# Self_Balancing_Bot1.net
KiCad netlist of a schematic drawn in EAGLE
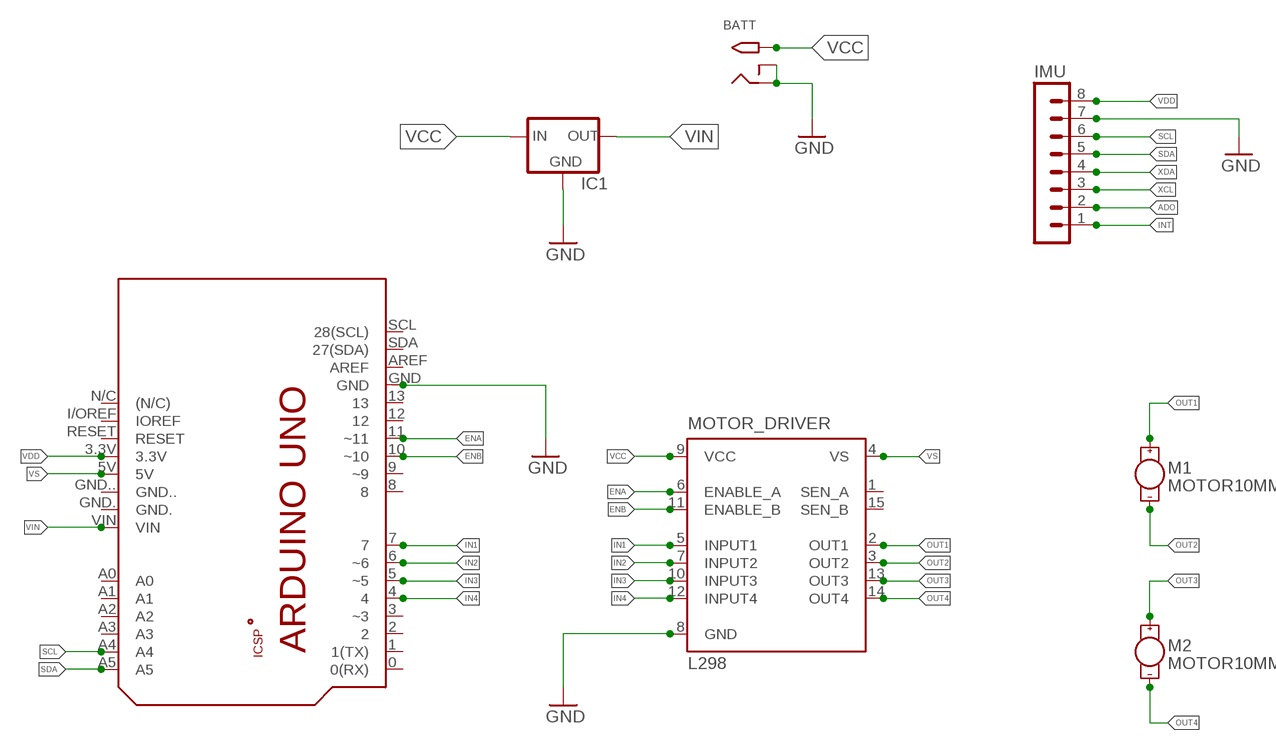
[diagram p0: schematic, sheet 1]

(export (version "E")
  (design (tool "Eeschema 10.0.6"))
  (components
    (comp (ref "ARDUINO_UNO")
      (value "ARDUINO_UNO")
      (footprint "eagle-import:ARDUINO_UNO")
      (libsource (lib "eagle-import") (part "ARDUINO_UNO"))
    )
    (comp (ref "BATT")
      (value "2.1MM_POWER_JACKTHM")
      (footprint "eagle-import:POWER_JACK")
      (libsource (lib "eagle-import") (part "2.1MM_POWER_JACKTHM"))
    )
    (comp (ref "IC1")
      (value "VOLTAGE_REGULATOR_78XXS")
      (footprint "eagle-import:78XXS")
      (libsource (lib "eagle-import") (part "VOLTAGE_REGULATOR_78XXS"))
    )
    (comp (ref "IMU")
      (value "RELIMATE_08-1")
      (footprint "eagle-import:MA08-1")
      (libsource (lib "eagle-import") (part "RELIMATE_08-1"))
    )
    (comp (ref "M1")
      (value "MOTOR10MM")
      (footprint "eagle-import:VIBE-MOTOR-10MM")
      (libsource (lib "eagle-import") (part "MOTOR10MM"))
    )
    (comp (ref "M2")
      (value "MOTOR10MM")
      (footprint "eagle-import:VIBE-MOTOR-10MM")
      (libsource (lib "eagle-import") (part "MOTOR10MM"))
    )
    (comp (ref "MOTOR_DRIVER")
      (value "L298")
      (footprint "eagle-import:MULTIWATT-15")
      (libsource (lib "eagle-import") (part "L298"))
    )
  )
  (nets
    (net (code "1") (name "ADO") (class "Default")
      (node (ref "IMU") (pin "2") (pinfunction "2_2") (pintype "passive"))
    )
    (net (code "2") (name "ENA") (class "Default")
      (node (ref "ARDUINO_UNO") (pin "11") (pinfunction "~{11}_11") (pintype "bidirectional"))
      (node (ref "MOTOR_DRIVER") (pin "6") (pinfunction "ENABLE_A_6") (pintype "input"))
    )
    (net (code "3") (name "ENB") (class "Default")
      (node (ref "ARDUINO_UNO") (pin "10") (pinfunction "~{10}_10") (pintype "bidirectional"))
      (node (ref "MOTOR_DRIVER") (pin "11") (pinfunction "ENABLE_B_11") (pintype "input"))
    )
    (net (code "4") (name "GND") (class "Default")
      (node (ref "ARDUINO_UNO") (pin "GND") (pinfunction "GND_GND") (pintype "bidirectional"))
      (node (ref "BATT") (pin "RING") (pinfunction "RING_RING") (pintype "bidirectional"))
      (node (ref "BATT") (pin "RING_SW") (pinfunction "RING_SW_RING_SW") (pintype "bidirectional"))
      (node (ref "IC1") (pin "GND") (pinfunction "GND_GND") (pintype "input"))
      (node (ref "IMU") (pin "7") (pinfunction "7_7") (pintype "passive"))
      (node (ref "MOTOR_DRIVER") (pin "8") (pinfunction "GND_8") (pintype "power_in"))
    )
    (net (code "5") (name "IN1") (class "Default")
      (node (ref "ARDUINO_UNO") (pin "7") (pinfunction "7_7") (pintype "bidirectional"))
      (node (ref "MOTOR_DRIVER") (pin "5") (pinfunction "INPUT1_5") (pintype "input"))
    )
    (net (code "6") (name "IN2") (class "Default")
      (node (ref "ARDUINO_UNO") (pin "6") (pinfunction "~{6}_6") (pintype "bidirectional"))
      (node (ref "MOTOR_DRIVER") (pin "7") (pinfunction "INPUT2_7") (pintype "input"))
    )
    (net (code "7") (name "IN3") (class "Default")
      (node (ref "ARDUINO_UNO") (pin "5") (pinfunction "~{5}_5") (pintype "bidirectional"))
      (node (ref "MOTOR_DRIVER") (pin "10") (pinfunction "INPUT3_10") (pintype "input"))
    )
    (net (code "8") (name "IN4") (class "Default")
      (node (ref "ARDUINO_UNO") (pin "4") (pinfunction "4_4") (pintype "bidirectional"))
      (node (ref "MOTOR_DRIVER") (pin "12") (pinfunction "INPUT4_12") (pintype "input"))
    )
    (net (code "9") (name "INT") (class "Default")
      (node (ref "IMU") (pin "1") (pinfunction "1_1") (pintype "passive"))
    )
    (net (code "10") (name "OUT1") (class "Default")
      (node (ref "M1") (pin "+") (pinfunction "+_+") (pintype "bidirectional"))
      (node (ref "MOTOR_DRIVER") (pin "2") (pinfunction "OUT1_2") (pintype "output"))
    )
    (net (code "11") (name "OUT2") (class "Default")
      (node (ref "M1") (pin "-") (pinfunction "-_-") (pintype "bidirectional"))
      (node (ref "MOTOR_DRIVER") (pin "3") (pinfunction "OUT2_3") (pintype "output"))
    )
    (net (code "12") (name "OUT3") (class "Default")
      (node (ref "M2") (pin "+") (pinfunction "+_+") (pintype "bidirectional"))
      (node (ref "MOTOR_DRIVER") (pin "13") (pinfunction "OUT3_13") (pintype "output"))
    )
    (net (code "13") (name "OUT4") (class "Default")
      (node (ref "M2") (pin "-") (pinfunction "-_-") (pintype "bidirectional"))
      (node (ref "MOTOR_DRIVER") (pin "14") (pinfunction "OUT4_14") (pintype "output"))
    )
    (net (code "14") (name "SCL") (class "Default")
      (node (ref "ARDUINO_UNO") (pin "A4") (pinfunction "A4_A4") (pintype "bidirectional"))
      (node (ref "IMU") (pin "6") (pinfunction "6_6") (pintype "passive"))
    )
    (net (code "15") (name "SDA") (class "Default")
      (node (ref "ARDUINO_UNO") (pin "A5") (pinfunction "A5_A5") (pintype "bidirectional"))
      (node (ref "IMU") (pin "5") (pinfunction "5_5") (pintype "passive"))
    )
    (net (code "16") (name "VCC") (class "Default")
      (node (ref "BATT") (pin "TIP") (pinfunction "TIP_TIP") (pintype "bidirectional"))
      (node (ref "IC1") (pin "IN") (pinfunction "IN_IN") (pintype "input"))
      (node (ref "MOTOR_DRIVER") (pin "9") (pinfunction "VCC_9") (pintype "power_in"))
    )
    (net (code "17") (name "VDD") (class "Default")
      (node (ref "ARDUINO_UNO") (pin "3.3V") (pinfunction "3.3V_3.3V") (pintype "bidirectional"))
      (node (ref "IMU") (pin "8") (pinfunction "8_8") (pintype "passive"))
    )
    (net (code "18") (name "VIN") (class "Default")
      (node (ref "ARDUINO_UNO") (pin "VIN") (pinfunction "VIN_VIN") (pintype "bidirectional"))
      (node (ref "IC1") (pin "OUT") (pinfunction "OUT_OUT") (pintype "passive"))
    )
    (net (code "19") (name "VS") (class "Default")
      (node (ref "ARDUINO_UNO") (pin "5V") (pinfunction "5V_5V") (pintype "bidirectional"))
      (node (ref "MOTOR_DRIVER") (pin "4") (pinfunction "VS_4") (pintype "power_in"))
    )
    (net (code "20") (name "XCL") (class "Default")
      (node (ref "IMU") (pin "3") (pinfunction "3_3") (pintype "passive"))
    )
    (net (code "21") (name "XDA") (class "Default")
      (node (ref "IMU") (pin "4") (pinfunction "4_4") (pintype "passive"))
    )
    (net (code "22") (name "unconnected-(ARDUINO_UNO-(N{slash}C)-PadN{slash}C)") (class "Default")
      (node (ref "ARDUINO_UNO") (pin "N/C") (pinfunction "(N/C)_N/C") (pintype "bidirectional"))
    )
    (net (code "23") (name "unconnected-(ARDUINO_UNO-0(RX)-Pad0)") (class "Default")
      (node (ref "ARDUINO_UNO") (pin "0") (pinfunction "0(RX)_0") (pintype "bidirectional"))
    )
    (net (code "24") (name "unconnected-(ARDUINO_UNO-1(TX)-Pad1)") (class "Default")
      (node (ref "ARDUINO_UNO") (pin "1") (pinfunction "1(TX)_1") (pintype "bidirectional"))
    )
    (net (code "25") (name "unconnected-(ARDUINO_UNO-27(SDA)-PadSDA)") (class "Default")
      (node (ref "ARDUINO_UNO") (pin "SDA") (pinfunction "27(SDA)_SDA") (pintype "bidirectional"))
    )
    (net (code "26") (name "unconnected-(ARDUINO_UNO-28(SCL)-PadSCL)") (class "Default")
      (node (ref "ARDUINO_UNO") (pin "SCL") (pinfunction "28(SCL)_SCL") (pintype "bidirectional"))
    )
    (net (code "27") (name "unconnected-(ARDUINO_UNO-IOREF-PadI{slash}OREF)") (class "Default")
      (node (ref "ARDUINO_UNO") (pin "I/OREF") (pinfunction "IOREF_I/OREF") (pintype "bidirectional"))
    )
    (net (code "28") (name "unconnected-(ARDUINO_UNO-Pad+5V)") (class "Default")
      (node (ref "ARDUINO_UNO") (pin "+5V") (pinfunction "+5V_+5V") (pintype "bidirectional"))
    )
    (net (code "29") (name "unconnected-(ARDUINO_UNO-Pad2)") (class "Default")
      (node (ref "ARDUINO_UNO") (pin "2") (pinfunction "2_2") (pintype "bidirectional"))
    )
    (net (code "30") (name "unconnected-(ARDUINO_UNO-Pad8)") (class "Default")
      (node (ref "ARDUINO_UNO") (pin "8") (pinfunction "8_8") (pintype "bidirectional"))
    )
    (net (code "31") (name "unconnected-(ARDUINO_UNO-Pad12)") (class "Default")
      (node (ref "ARDUINO_UNO") (pin "12") (pinfunction "12_12") (pintype "bidirectional"))
    )
    (net (code "32") (name "unconnected-(ARDUINO_UNO-Pad13)") (class "Default")
      (node (ref "ARDUINO_UNO") (pin "13") (pinfunction "13_13") (pintype "bidirectional"))
    )
    (net (code "33") (name "unconnected-(ARDUINO_UNO-PadA0)") (class "Default")
      (node (ref "ARDUINO_UNO") (pin "A0") (pinfunction "A0_A0") (pintype "bidirectional"))
    )
    (net (code "34") (name "unconnected-(ARDUINO_UNO-PadA1)") (class "Default")
      (node (ref "ARDUINO_UNO") (pin "A1") (pinfunction "A1_A1") (pintype "bidirectional"))
    )
    (net (code "35") (name "unconnected-(ARDUINO_UNO-PadA2)") (class "Default")
      (node (ref "ARDUINO_UNO") (pin "A2") (pinfunction "A2_A2") (pintype "bidirectional"))
    )
    (net (code "36") (name "unconnected-(ARDUINO_UNO-PadA3)") (class "Default")
      (node (ref "ARDUINO_UNO") (pin "A3") (pinfunction "A3_A3") (pintype "bidirectional"))
    )
    (net (code "37") (name "unconnected-(ARDUINO_UNO-PadAREF)") (class "Default")
      (node (ref "ARDUINO_UNO") (pin "AREF") (pinfunction "AREF_AREF") (pintype "bidirectional"))
    )
    (net (code "38") (name "unconnected-(ARDUINO_UNO-PadGND.)") (class "Default")
      (node (ref "ARDUINO_UNO") (pin "GND.") (pinfunction "GND._GND.") (pintype "bidirectional"))
    )
    (net (code "39") (name "unconnected-(ARDUINO_UNO-PadGND..)") (class "Default")
      (node (ref "ARDUINO_UNO") (pin "GND..") (pinfunction "GND.._GND..") (pintype "bidirectional"))
    )
    (net (code "40") (name "unconnected-(ARDUINO_UNO-PadGND_)") (class "Default")
      (node (ref "ARDUINO_UNO") (pin "GND_") (pinfunction "GND__GND_") (pintype "bidirectional"))
    )
    (net (code "41") (name "unconnected-(ARDUINO_UNO-PadMISO)") (class "Default")
      (node (ref "ARDUINO_UNO") (pin "MISO") (pinfunction "MISO_MISO") (pintype "bidirectional"))
    )
    (net (code "42") (name "unconnected-(ARDUINO_UNO-PadMOSI)") (class "Default")
      (node (ref "ARDUINO_UNO") (pin "MOSI") (pinfunction "MOSI_MOSI") (pintype "bidirectional"))
    )
    (net (code "43") (name "unconnected-(ARDUINO_UNO-PadRESET)") (class "Default")
      (node (ref "ARDUINO_UNO") (pin "RESET") (pinfunction "RESET_RESET") (pintype "bidirectional"))
    )
    (net (code "44") (name "unconnected-(ARDUINO_UNO-PadRESET.)") (class "Default")
      (node (ref "ARDUINO_UNO") (pin "RESET.") (pinfunction "RESET._RESET.") (pintype "bidirectional"))
    )
    (net (code "45") (name "unconnected-(ARDUINO_UNO-PadSCK)") (class "Default")
      (node (ref "ARDUINO_UNO") (pin "SCK") (pinfunction "SCK_SCK") (pintype "bidirectional"))
    )
    (net (code "46") (name "unconnected-(ARDUINO_UNO-~{3}-Pad3)") (class "Default")
      (node (ref "ARDUINO_UNO") (pin "3") (pinfunction "~{3}_3") (pintype "bidirectional"))
    )
    (net (code "47") (name "unconnected-(ARDUINO_UNO-~{9}-Pad9)") (class "Default")
      (node (ref "ARDUINO_UNO") (pin "9") (pinfunction "~{9}_9") (pintype "bidirectional"))
    )
    (net (code "48") (name "unconnected-(MOTOR_DRIVER-SEN_A-Pad1)") (class "Default")
      (node (ref "MOTOR_DRIVER") (pin "1") (pinfunction "SEN_A_1") (pintype "input"))
    )
    (net (code "49") (name "unconnected-(MOTOR_DRIVER-SEN_B-Pad15)") (class "Default")
      (node (ref "MOTOR_DRIVER") (pin "15") (pinfunction "SEN_B_15") (pintype "input"))
    )
  )
)
